# TakpadV6.net
KiCad netlist of a schematic drawn in EAGLE
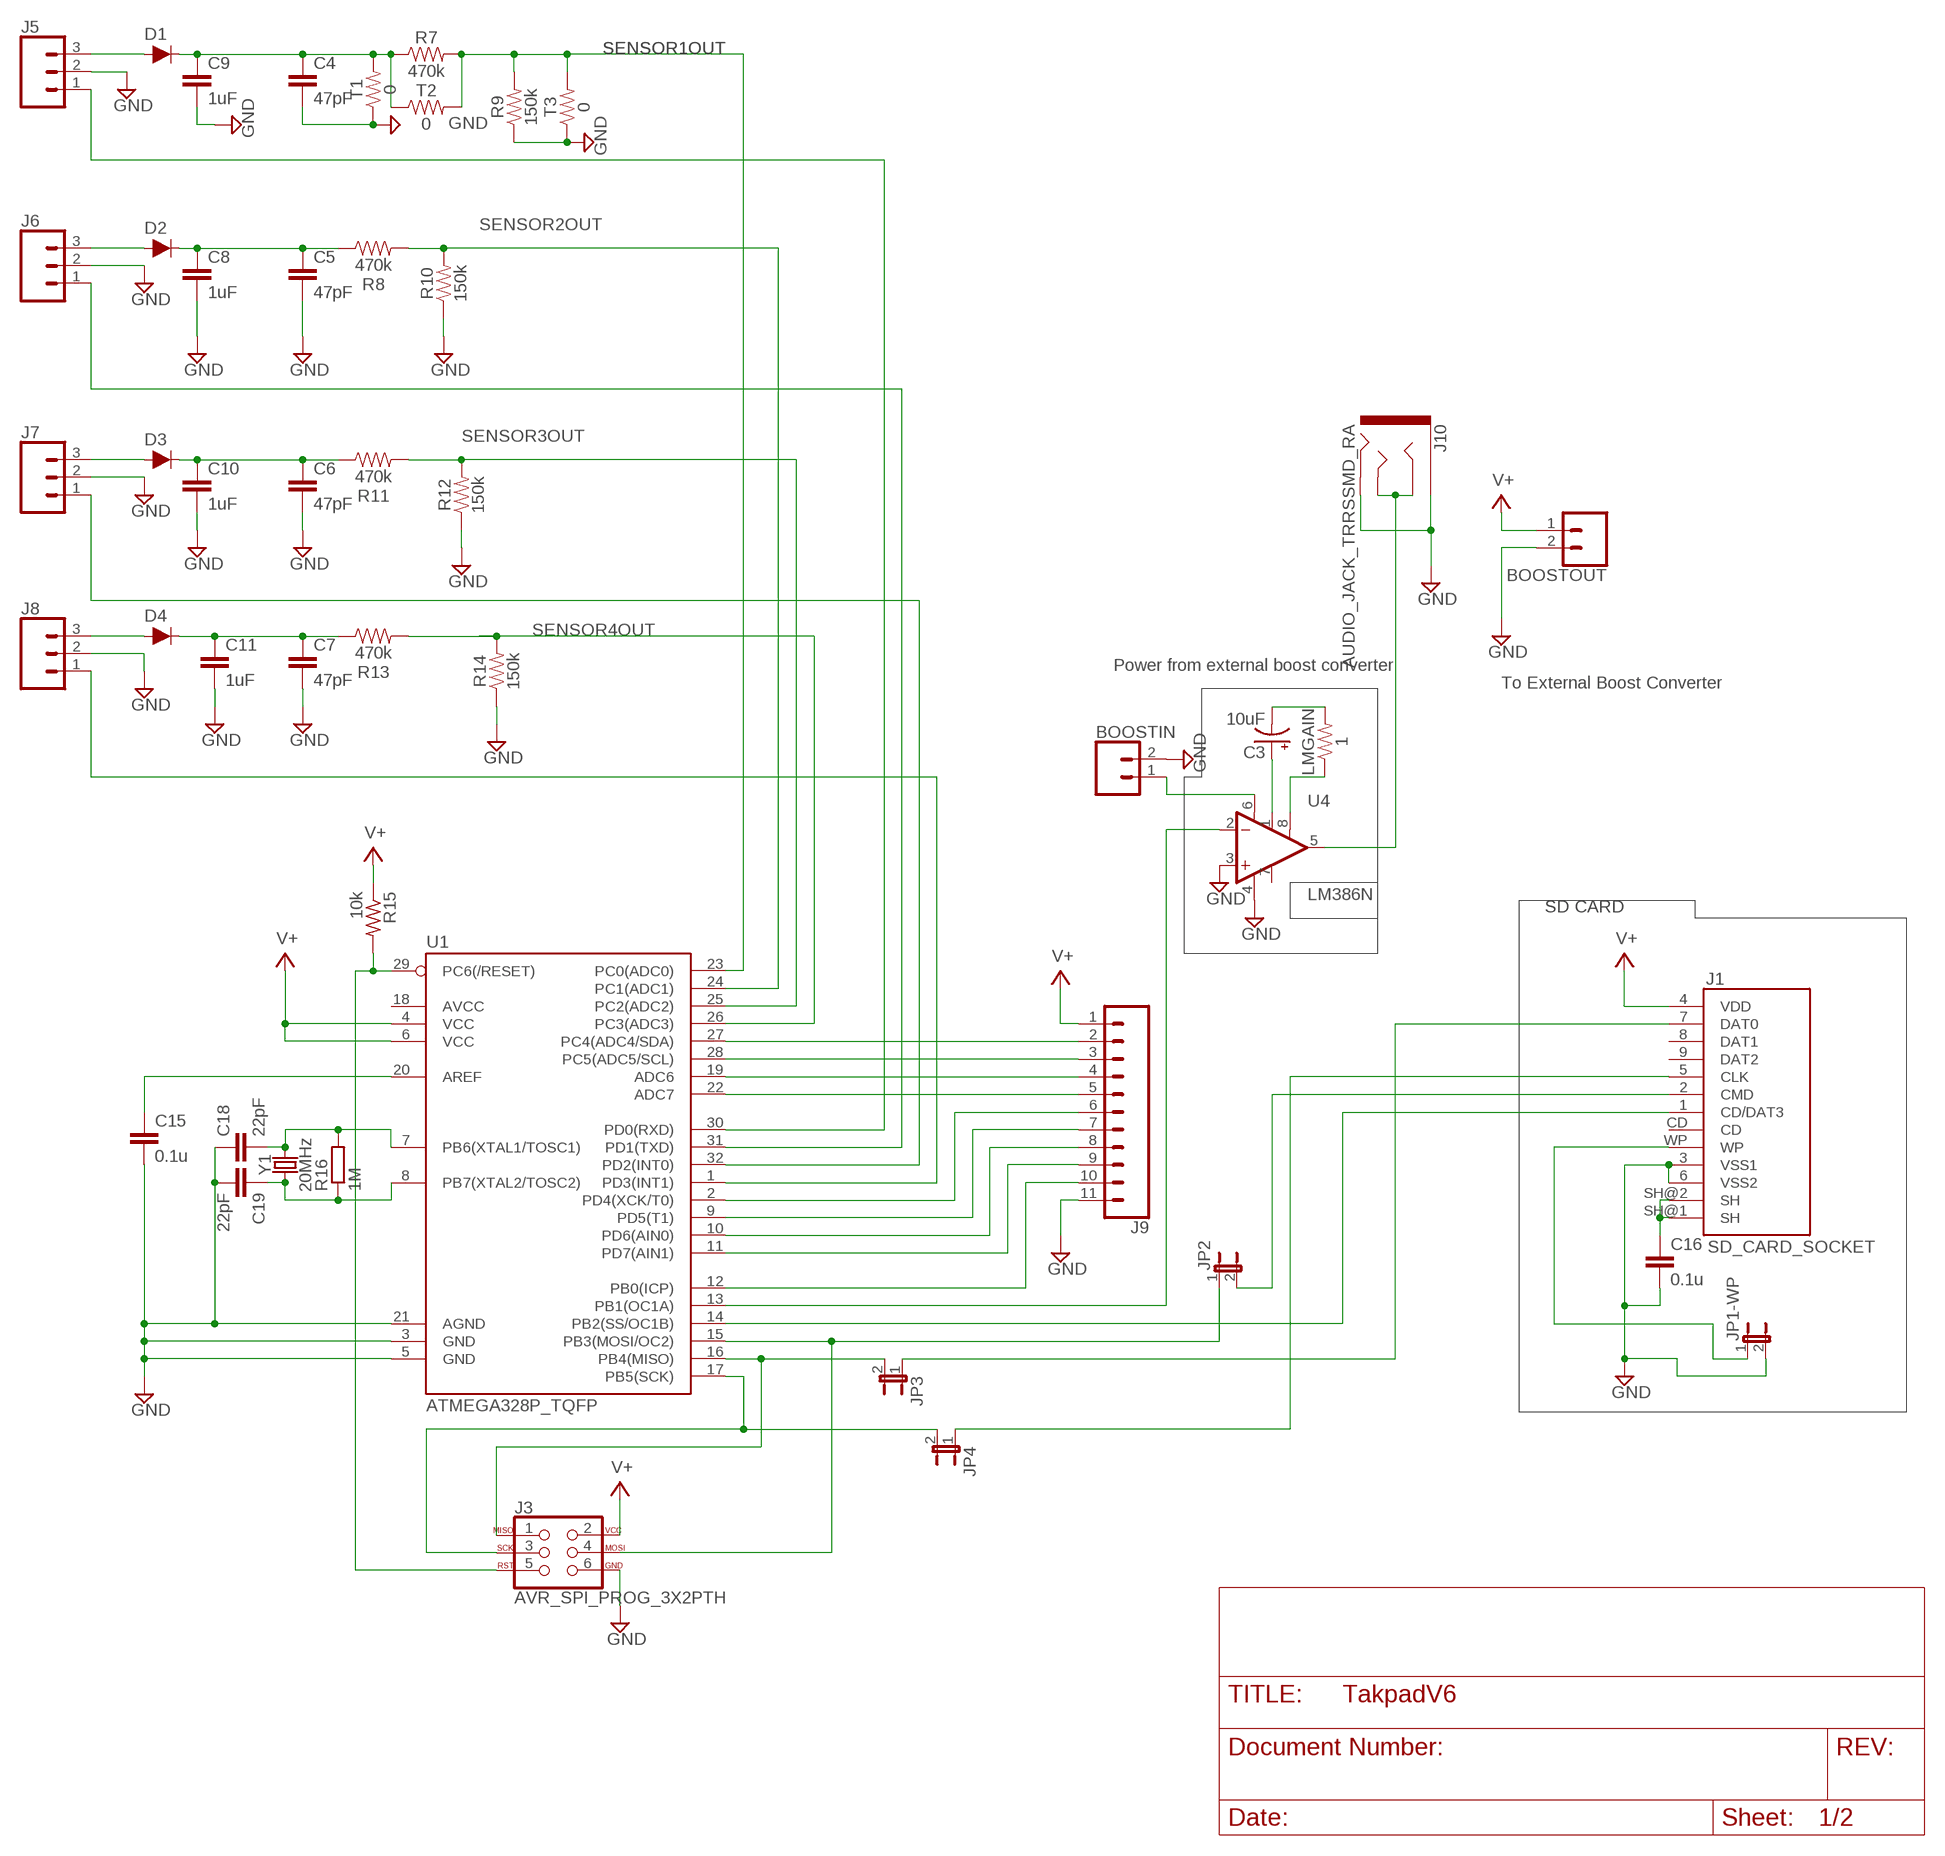
[diagram p0: schematic, sheet 1]
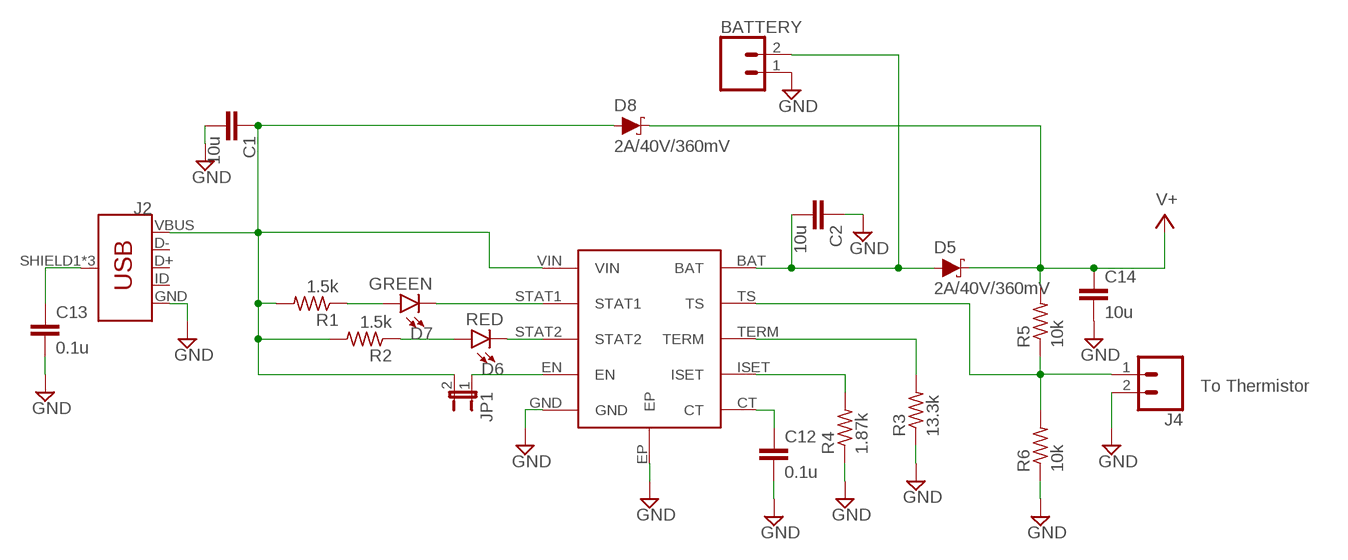
[diagram p1: schematic, sheet 2]

(export (version "E")
  (design (tool "Eeschema 10.0.6"))
  (components
    (comp (ref "BATTERY")
      (value "CONN_02")
      (footprint "eagle-import:1X02")
      (libsource (lib "eagle-import") (part "CONN_02"))
    )
    (comp (ref "C1")
      (value "10u")
      (footprint "eagle-import:C0402")
      (libsource (lib "eagle-import") (part "C-EUC0402"))
    )
    (comp (ref "C2")
      (value "10u")
      (footprint "eagle-import:C0402")
      (libsource (lib "eagle-import") (part "C-EUC0402"))
    )
    (comp (ref "C12")
      (value "0.1u")
      (footprint "eagle-import:C0402")
      (libsource (lib "eagle-import") (part "C-EUC0402"))
    )
    (comp (ref "C13")
      (value "0.1u")
      (footprint "eagle-import:C0402")
      (libsource (lib "eagle-import") (part "C-EUC0402"))
    )
    (comp (ref "C14")
      (value "10u")
      (footprint "eagle-import:C0402")
      (libsource (lib "eagle-import") (part "C-EUC0402"))
    )
    (comp (ref "D5")
      (value "2A/40V/360mV")
      (footprint "eagle-import:SMA-DIODE")
      (libsource (lib "eagle-import") (part "DIODE-SCHOTTKY-B340A"))
    )
    (comp (ref "D6")
      (value "RED")
      (footprint "eagle-import:LED-1206")
      (libsource (lib "eagle-import") (part "LED-RED1206"))
    )
    (comp (ref "D7")
      (value "GREEN")
      (footprint "eagle-import:LED-1206")
      (libsource (lib "eagle-import") (part "LED-GREEN1206"))
    )
    (comp (ref "D8")
      (value "2A/40V/360mV")
      (footprint "eagle-import:SMA-DIODE")
      (libsource (lib "eagle-import") (part "DIODE-SCHOTTKY-B340A"))
    )
    (comp (ref "J2")
      (value "USB_MICRO-BREDUCED_PASTE")
      (footprint "eagle-import:USB-B-MICRO-SMD_RED_PASTE")
      (libsource (lib "eagle-import") (part "USB_MICRO-BREDUCED_PASTE"))
    )
    (comp (ref "J4")
      (value "CONN_02")
      (footprint "eagle-import:1X02")
      (libsource (lib "eagle-import") (part "CONN_02"))
    )
    (comp (ref "JP1")
      (value "JUMPER-2PTH")
      (footprint "eagle-import:1X02")
      (libsource (lib "eagle-import") (part "JUMPER-2PTH"))
    )
    (comp (ref "R1")
      (value "1.5k")
      (footprint "eagle-import:M1206")
      (libsource (lib "eagle-import") (part "R-US_M1206"))
    )
    (comp (ref "R2")
      (value "1.5k")
      (footprint "eagle-import:M1206")
      (libsource (lib "eagle-import") (part "R-US_M1206"))
    )
    (comp (ref "R3")
      (value "13.3k")
      (footprint "eagle-import:M1206")
      (libsource (lib "eagle-import") (part "R-US_M1206"))
    )
    (comp (ref "R4")
      (value "1.87k")
      (footprint "eagle-import:M1206")
      (libsource (lib "eagle-import") (part "R-US_M1206"))
    )
    (comp (ref "R5")
      (value "10k")
      (footprint "eagle-import:M1206")
      (libsource (lib "eagle-import") (part "R-US_M1206"))
    )
    (comp (ref "R6")
      (value "10k")
      (footprint "eagle-import:M1206")
      (libsource (lib "eagle-import") (part "R-US_M1206"))
    )
    (comp (ref "U$1")
      (value "AAT3693")
      (footprint "eagle-import:IDH-AA-T1")
      (libsource (lib "eagle-import") (part "AAT3693"))
    )
    (comp (ref "BOOSTIN")
      (value "CONN_02")
      (footprint "eagle-import:1X02")
      (libsource (lib "eagle-import") (part "CONN_02"))
    )
    (comp (ref "BOOSTOUT")
      (value "CONN_02")
      (footprint "eagle-import:1X02")
      (libsource (lib "eagle-import") (part "CONN_02"))
    )
    (comp (ref "C3")
      (value "10uF")
      (footprint "eagle-import:CPOL-RADIAL-2.5MM-5MM-KIT")
      (libsource (lib "eagle-import") (part "10UF-POLAR-RADIAL-2.5MM-KIT-25V-20%"))
    )
    (comp (ref "C4")
      (value "47pF")
      (footprint "eagle-import:0603")
      (libsource (lib "eagle-import") (part "47PF-0603-50V-5%"))
    )
    (comp (ref "C5")
      (value "47pF")
      (footprint "eagle-import:0603")
      (libsource (lib "eagle-import") (part "47PF-0603-50V-5%"))
    )
    (comp (ref "C6")
      (value "47pF")
      (footprint "eagle-import:0603")
      (libsource (lib "eagle-import") (part "47PF-0603-50V-5%"))
    )
    (comp (ref "C7")
      (value "47pF")
      (footprint "eagle-import:0603")
      (libsource (lib "eagle-import") (part "47PF-0603-50V-5%"))
    )
    (comp (ref "C8")
      (value "1uF")
      (footprint "eagle-import:0603")
      (libsource (lib "eagle-import") (part "47PF-0603-50V-5%"))
    )
    (comp (ref "C9")
      (value "1uF")
      (footprint "eagle-import:0603")
      (libsource (lib "eagle-import") (part "47PF-0603-50V-5%"))
    )
    (comp (ref "C10")
      (value "1uF")
      (footprint "eagle-import:0603")
      (libsource (lib "eagle-import") (part "47PF-0603-50V-5%"))
    )
    (comp (ref "C11")
      (value "1uF")
      (footprint "eagle-import:0603")
      (libsource (lib "eagle-import") (part "47PF-0603-50V-5%"))
    )
    (comp (ref "C15")
      (value "0.1u")
      (footprint "eagle-import:C0402")
      (libsource (lib "eagle-import") (part "C-EUC0402"))
    )
    (comp (ref "C16")
      (value "0.1u")
      (footprint "eagle-import:C0402")
      (libsource (lib "eagle-import") (part "C-EUC0402"))
    )
    (comp (ref "C18")
      (value "22pF")
      (footprint "eagle-import:C0402")
      (libsource (lib "eagle-import") (part "resistor_348_C-EUC0402"))
    )
    (comp (ref "C19")
      (value "22pF")
      (footprint "eagle-import:C0402")
      (libsource (lib "eagle-import") (part "resistor_348_C-EUC0402"))
    )
    (comp (ref "D1")
      (value "200mA/100V/1V")
      (footprint "eagle-import:DIODE-1N4148")
      (libsource (lib "eagle-import") (part "DIODE-1N4148"))
    )
    (comp (ref "D2")
      (value "200mA/100V/1V")
      (footprint "eagle-import:DIODE-1N4148")
      (libsource (lib "eagle-import") (part "DIODE-1N4148"))
    )
    (comp (ref "D3")
      (value "200mA/100V/1V")
      (footprint "eagle-import:DIODE-1N4148")
      (libsource (lib "eagle-import") (part "DIODE-1N4148"))
    )
    (comp (ref "D4")
      (value "200mA/100V/1V")
      (footprint "eagle-import:DIODE-1N4148")
      (libsource (lib "eagle-import") (part "DIODE-1N4148"))
    )
    (comp (ref "J1")
      (value "SD_CARD_SOCKET")
      (footprint "eagle-import:SD")
      (libsource (lib "eagle-import") (part "SD_CARD_SOCKET"))
    )
    (comp (ref "J3")
      (value "AVR_SPI_PROG_3X2PTH")
      (footprint "eagle-import:2X3")
      (libsource (lib "eagle-import") (part "AVR_SPI_PROG_3X2PTH"))
    )
    (comp (ref "J5")
      (value "CONN_03")
      (footprint "eagle-import:1X03")
      (libsource (lib "eagle-import") (part "CONN_03"))
    )
    (comp (ref "J6")
      (value "CONN_03")
      (footprint "eagle-import:1X03")
      (libsource (lib "eagle-import") (part "CONN_03"))
    )
    (comp (ref "J7")
      (value "CONN_03")
      (footprint "eagle-import:1X03")
      (libsource (lib "eagle-import") (part "CONN_03"))
    )
    (comp (ref "J8")
      (value "CONN_03")
      (footprint "eagle-import:1X03")
      (libsource (lib "eagle-import") (part "CONN_03"))
    )
    (comp (ref "J9")
      (value "CONN_11")
      (footprint "eagle-import:1X11")
      (libsource (lib "eagle-import") (part "CONN_11"))
    )
    (comp (ref "J10")
      (value "AUDIO_JACK_TRRSSMD_RA")
      (footprint "eagle-import:AUDIO_JACK_3.5MM_TRRS_SMD_RA")
      (libsource (lib "eagle-import") (part "AUDIO_JACK_TRRSSMD_RA"))
    )
    (comp (ref "JP1-WP")
      (value "JUMPER-2PTH")
      (footprint "eagle-import:1X02")
      (libsource (lib "eagle-import") (part "JUMPER-2PTH"))
    )
    (comp (ref "JP2")
      (value "JUMPER-2PTH")
      (footprint "eagle-import:1X02")
      (libsource (lib "eagle-import") (part "JUMPER-2PTH"))
    )
    (comp (ref "JP3")
      (value "JUMPER-2PTH")
      (footprint "eagle-import:1X02")
      (libsource (lib "eagle-import") (part "JUMPER-2PTH"))
    )
    (comp (ref "JP4")
      (value "JUMPER-2PTH")
      (footprint "eagle-import:1X02")
      (libsource (lib "eagle-import") (part "JUMPER-2PTH"))
    )
    (comp (ref "LMGAIN")
      (value "1")
      (footprint "eagle-import:0603")
      (libsource (lib "eagle-import") (part "1OHM-0603-1/10W-1%"))
    )
    (comp (ref "R7")
      (value "470k")
      (footprint "eagle-import:AXIAL-0.3")
      (libsource (lib "eagle-import") (part "1KOHM-HORIZ-1/4W-1%"))
    )
    (comp (ref "R8")
      (value "470k")
      (footprint "eagle-import:AXIAL-0.3")
      (libsource (lib "eagle-import") (part "1KOHM-HORIZ-1/4W-1%"))
    )
    (comp (ref "R9")
      (value "150k")
      (footprint "eagle-import:AXIAL-0.3")
      (libsource (lib "eagle-import") (part "1KOHM-HORIZ-1/4W-1%"))
    )
    (comp (ref "R10")
      (value "150k")
      (footprint "eagle-import:AXIAL-0.3")
      (libsource (lib "eagle-import") (part "1KOHM-HORIZ-1/4W-1%"))
    )
    (comp (ref "R11")
      (value "470k")
      (footprint "eagle-import:AXIAL-0.3")
      (libsource (lib "eagle-import") (part "1KOHM-HORIZ-1/4W-1%"))
    )
    (comp (ref "R12")
      (value "150k")
      (footprint "eagle-import:AXIAL-0.3")
      (libsource (lib "eagle-import") (part "1KOHM-HORIZ-1/4W-1%"))
    )
    (comp (ref "R13")
      (value "470k")
      (footprint "eagle-import:AXIAL-0.3")
      (libsource (lib "eagle-import") (part "1KOHM-HORIZ-1/4W-1%"))
    )
    (comp (ref "R14")
      (value "150k")
      (footprint "eagle-import:AXIAL-0.3")
      (libsource (lib "eagle-import") (part "1KOHM-HORIZ-1/4W-1%"))
    )
    (comp (ref "R15")
      (value "10k")
      (footprint "eagle-import:M1206")
      (libsource (lib "eagle-import") (part "R-US_M1206"))
    )
    (comp (ref "R16")
      (value "1M")
      (footprint "eagle-import:R0402")
      (libsource (lib "eagle-import") (part "R-EU_R0402"))
    )
    (comp (ref "T1")
      (value "0")
      (footprint "eagle-import:AXIAL-0.3")
      (libsource (lib "eagle-import") (part "1KOHM-HORIZ-1/4W-1%"))
    )
    (comp (ref "T2")
      (value "0")
      (footprint "eagle-import:AXIAL-0.3")
      (libsource (lib "eagle-import") (part "1KOHM-HORIZ-1/4W-1%"))
    )
    (comp (ref "T3")
      (value "0")
      (footprint "eagle-import:AXIAL-0.3")
      (libsource (lib "eagle-import") (part "1KOHM-HORIZ-1/4W-1%"))
    )
    (comp (ref "U1")
      (value "ATMEGA328P_TQFP")
      (footprint "eagle-import:TQFP32-08")
      (libsource (lib "eagle-import") (part "ATMEGA328P_TQFP"))
    )
    (comp (ref "U4")
      (value "LM386N")
      (footprint "eagle-import:DIP08")
      (libsource (lib "eagle-import") (part "LM386"))
    )
    (comp (ref "Y1")
      (value "20MHz")
      (footprint "eagle-import:HC49US")
      (libsource (lib "eagle-import") (part "CRYSTAL-16MHZPTH-HC49US"))
    )
  )
  (nets
    (net (code "1") (name "GND") (class "Default")
      (node (ref "BATTERY") (pin "1") (pinfunction "1_1") (pintype "passive"))
      (node (ref "BOOSTIN") (pin "2") (pinfunction "2_2") (pintype "passive"))
      (node (ref "BOOSTOUT") (pin "2") (pinfunction "2_2") (pintype "passive"))
      (node (ref "C1") (pin "2") (pinfunction "2_2") (pintype "passive"))
      (node (ref "C10") (pin "2") (pinfunction "2_2") (pintype "passive"))
      (node (ref "C11") (pin "2") (pinfunction "2_2") (pintype "passive"))
      (node (ref "C12") (pin "2") (pinfunction "2_2") (pintype "passive"))
      (node (ref "C13") (pin "2") (pinfunction "2_2") (pintype "passive"))
      (node (ref "C14") (pin "2") (pinfunction "2_2") (pintype "passive"))
      (node (ref "C15") (pin "2") (pinfunction "2_2") (pintype "passive"))
      (node (ref "C16") (pin "2") (pinfunction "2_2") (pintype "passive"))
      (node (ref "C18") (pin "1") (pinfunction "1_1") (pintype "passive"))
      (node (ref "C19") (pin "2") (pinfunction "2_2") (pintype "passive"))
      (node (ref "C2") (pin "1") (pinfunction "1_1") (pintype "passive"))
      (node (ref "C4") (pin "2") (pinfunction "2_2") (pintype "passive"))
      (node (ref "C5") (pin "2") (pinfunction "2_2") (pintype "passive"))
      (node (ref "C6") (pin "2") (pinfunction "2_2") (pintype "passive"))
      (node (ref "C7") (pin "2") (pinfunction "2_2") (pintype "passive"))
      (node (ref "C8") (pin "2") (pinfunction "2_2") (pintype "passive"))
      (node (ref "C9") (pin "2") (pinfunction "2_2") (pintype "passive"))
      (node (ref "J1") (pin "3") (pinfunction "VSS1_3") (pintype "power_in"))
      (node (ref "J1") (pin "6") (pinfunction "VSS2_6") (pintype "power_in"))
      (node (ref "J10") (pin "EARTH") (pinfunction "EARTH_EARTH") (pintype "bidirectional"))
      (node (ref "J10") (pin "RING2") (pinfunction "RING2_RING2") (pintype "bidirectional"))
      (node (ref "J2") (pin "GND") (pinfunction "GND_GND") (pintype "power_in"))
      (node (ref "J3") (pin "6") (pinfunction "6_6") (pintype "passive"))
      (node (ref "J4") (pin "2") (pinfunction "2_2") (pintype "passive"))
      (node (ref "J5") (pin "2") (pinfunction "2_2") (pintype "passive"))
      (node (ref "J6") (pin "2") (pinfunction "2_2") (pintype "passive"))
      (node (ref "J7") (pin "2") (pinfunction "2_2") (pintype "passive"))
      (node (ref "J8") (pin "2") (pinfunction "2_2") (pintype "passive"))
      (node (ref "J9") (pin "11") (pinfunction "11_11") (pintype "passive"))
      (node (ref "JP1-WP") (pin "2") (pinfunction "2_2") (pintype "passive"))
      (node (ref "R10") (pin "P$1") (pinfunction "1_P$1") (pintype "passive"))
      (node (ref "R12") (pin "P$1") (pinfunction "1_P$1") (pintype "passive"))
      (node (ref "R14") (pin "P$1") (pinfunction "1_P$1") (pintype "passive"))
      (node (ref "R3") (pin "1") (pinfunction "1_1") (pintype "passive"))
      (node (ref "R4") (pin "1") (pinfunction "1_1") (pintype "passive"))
      (node (ref "R6") (pin "1") (pinfunction "1_1") (pintype "passive"))
      (node (ref "R9") (pin "P$1") (pinfunction "1_P$1") (pintype "passive"))
      (node (ref "T1") (pin "P$1") (pinfunction "1_P$1") (pintype "passive"))
      (node (ref "T3") (pin "P$1") (pinfunction "1_P$1") (pintype "passive"))
      (node (ref "U$1") (pin "EP") (pinfunction "EP_EP") (pintype "bidirectional"))
      (node (ref "U$1") (pin "GND") (pinfunction "GND_GND") (pintype "bidirectional"))
      (node (ref "U1") (pin "21") (pinfunction "AGND_21") (pintype "bidirectional"))
      (node (ref "U1") (pin "3") (pinfunction "GND_3") (pintype "bidirectional"))
      (node (ref "U1") (pin "5") (pinfunction "GND_5") (pintype "bidirectional"))
      (node (ref "U4") (pin "3") (pinfunction "+IN_3") (pintype "input"))
      (node (ref "U4") (pin "4") (pinfunction "V-_4") (pintype "power_in"))
    )
    (net (code "2") (name "Net-(BATTERY-Pad2)") (class "Default")
      (node (ref "BATTERY") (pin "2") (pinfunction "2_2") (pintype "passive"))
      (node (ref "C2") (pin "2") (pinfunction "2_2") (pintype "passive"))
      (node (ref "D5") (pin "A") (pinfunction "A_A") (pintype "passive"))
      (node (ref "U$1") (pin "BAT") (pinfunction "BAT_BAT") (pintype "bidirectional"))
    )
    (net (code "3") (name "Net-(C1-Pad1)") (class "Default")
      (node (ref "C1") (pin "1") (pinfunction "1_1") (pintype "passive"))
      (node (ref "D8") (pin "A") (pinfunction "A_A") (pintype "passive"))
      (node (ref "J2") (pin "VBUS") (pinfunction "VBUS_VBUS") (pintype "power_in"))
      (node (ref "JP1") (pin "2") (pinfunction "2_2") (pintype "passive"))
      (node (ref "R1") (pin "2") (pinfunction "2_2") (pintype "passive"))
      (node (ref "R2") (pin "2") (pinfunction "2_2") (pintype "passive"))
      (node (ref "U$1") (pin "VIN") (pinfunction "VIN_VIN") (pintype "bidirectional"))
    )
    (net (code "4") (name "Net-(C3-+)") (class "Default")
      (node (ref "C3") (pin "1") (pinfunction "+_1") (pintype "passive"))
      (node (ref "U4") (pin "1") (pinfunction "GAIN_1") (pintype "bidirectional"))
    )
    (net (code "5") (name "Net-(C3--)") (class "Default")
      (node (ref "C3") (pin "2") (pinfunction "-_2") (pintype "passive"))
      (node (ref "LMGAIN") (pin "2") (pinfunction "2_2") (pintype "passive"))
    )
    (net (code "6") (name "Net-(C12-Pad1)") (class "Default")
      (node (ref "C12") (pin "1") (pinfunction "1_1") (pintype "passive"))
      (node (ref "U$1") (pin "CT") (pinfunction "CT_CT") (pintype "bidirectional"))
    )
    (net (code "7") (name "Net-(C13-Pad1)") (class "Default")
      (node (ref "C13") (pin "1") (pinfunction "1_1") (pintype "passive"))
      (node (ref "J2") (pin "SHIELD1") (pinfunction "SHIELD_SHIELD1") (pintype "bidirectional"))
      (node (ref "J2") (pin "SHIELD2") (pinfunction "SHIELD_SHIELD2") (pintype "bidirectional"))
      (node (ref "J2") (pin "SHIELD3") (pinfunction "SHIELD_SHIELD3") (pintype "bidirectional"))
    )
    (net (code "8") (name "Net-(C16-Pad1)") (class "Default")
      (node (ref "C16") (pin "1") (pinfunction "1_1") (pintype "passive"))
      (node (ref "J1") (pin "SH@1") (pinfunction "SH_SH@1") (pintype "bidirectional"))
      (node (ref "J1") (pin "SH@2") (pinfunction "SH_SH@2") (pintype "bidirectional"))
    )
    (net (code "9") (name "Net-(D1-PadA)") (class "Default")
      (node (ref "D1") (pin "A") (pinfunction "A_A") (pintype "passive"))
      (node (ref "J5") (pin "3") (pinfunction "3_3") (pintype "passive"))
    )
    (net (code "10") (name "Net-(D2-PadA)") (class "Default")
      (node (ref "D2") (pin "A") (pinfunction "A_A") (pintype "passive"))
      (node (ref "J6") (pin "3") (pinfunction "3_3") (pintype "passive"))
    )
    (net (code "11") (name "Net-(D3-PadA)") (class "Default")
      (node (ref "D3") (pin "A") (pinfunction "A_A") (pintype "passive"))
      (node (ref "J7") (pin "3") (pinfunction "3_3") (pintype "passive"))
    )
    (net (code "12") (name "Net-(D4-PadA)") (class "Default")
      (node (ref "D4") (pin "A") (pinfunction "A_A") (pintype "passive"))
      (node (ref "J8") (pin "3") (pinfunction "3_3") (pintype "passive"))
    )
    (net (code "13") (name "Net-(D6-PadA)") (class "Default")
      (node (ref "D6") (pin "A") (pinfunction "A_A") (pintype "passive"))
      (node (ref "R2") (pin "1") (pinfunction "1_1") (pintype "passive"))
    )
    (net (code "14") (name "Net-(D6-PadC)") (class "Default")
      (node (ref "D6") (pin "C") (pinfunction "C_C") (pintype "passive"))
      (node (ref "U$1") (pin "STAT2") (pinfunction "STAT2_STAT2") (pintype "bidirectional"))
    )
    (net (code "15") (name "Net-(D7-PadA)") (class "Default")
      (node (ref "D7") (pin "A") (pinfunction "A_A") (pintype "passive"))
      (node (ref "R1") (pin "1") (pinfunction "1_1") (pintype "passive"))
    )
    (net (code "16") (name "Net-(D7-PadC)") (class "Default")
      (node (ref "D7") (pin "C") (pinfunction "C_C") (pintype "passive"))
      (node (ref "U$1") (pin "STAT1") (pinfunction "STAT1_STAT1") (pintype "bidirectional"))
    )
    (net (code "17") (name "Net-(J1-CD{slash}DAT3)") (class "Default")
      (node (ref "J1") (pin "1") (pinfunction "CD/DAT3_1") (pintype "bidirectional"))
      (node (ref "U1") (pin "14") (pinfunction "PB2(SS/OC1B)_14") (pintype "bidirectional"))
    )
    (net (code "18") (name "Net-(J1-CLK)") (class "Default")
      (node (ref "J1") (pin "5") (pinfunction "CLK_5") (pintype "bidirectional"))
      (node (ref "JP4") (pin "1") (pinfunction "1_1") (pintype "passive"))
    )
    (net (code "19") (name "Net-(J1-CMD)") (class "Default")
      (node (ref "J1") (pin "2") (pinfunction "CMD_2") (pintype "bidirectional"))
      (node (ref "JP2") (pin "2") (pinfunction "2_2") (pintype "passive"))
    )
    (net (code "20") (name "Net-(J1-DAT0)") (class "Default")
      (node (ref "J1") (pin "7") (pinfunction "DAT0_7") (pintype "bidirectional"))
      (node (ref "JP3") (pin "1") (pinfunction "1_1") (pintype "passive"))
    )
    (net (code "21") (name "Net-(J1-PadWP)") (class "Default")
      (node (ref "J1") (pin "WP") (pinfunction "WP_WP") (pintype "bidirectional"))
      (node (ref "JP1-WP") (pin "1") (pinfunction "1_1") (pintype "passive"))
    )
    (net (code "22") (name "Net-(J4-Pad1)") (class "Default")
      (node (ref "J4") (pin "1") (pinfunction "1_1") (pintype "passive"))
      (node (ref "R5") (pin "1") (pinfunction "1_1") (pintype "passive"))
      (node (ref "R6") (pin "2") (pinfunction "2_2") (pintype "passive"))
      (node (ref "U$1") (pin "TS") (pinfunction "TS_TS") (pintype "bidirectional"))
    )
    (net (code "23") (name "Net-(JP1-Pad1)") (class "Default")
      (node (ref "JP1") (pin "1") (pinfunction "1_1") (pintype "passive"))
      (node (ref "U$1") (pin "EN") (pinfunction "EN_EN") (pintype "bidirectional"))
    )
    (net (code "24") (name "Net-(LMGAIN-Pad1)") (class "Default")
      (node (ref "LMGAIN") (pin "1") (pinfunction "1_1") (pintype "passive"))
      (node (ref "U4") (pin "8") (pinfunction "GAIN_8") (pintype "bidirectional"))
    )
    (net (code "25") (name "Net-(R3-Pad2)") (class "Default")
      (node (ref "R3") (pin "2") (pinfunction "2_2") (pintype "passive"))
      (node (ref "U$1") (pin "TERM") (pinfunction "TERM_TERM") (pintype "bidirectional"))
    )
    (net (code "26") (name "Net-(R4-Pad2)") (class "Default")
      (node (ref "R4") (pin "2") (pinfunction "2_2") (pintype "passive"))
      (node (ref "U$1") (pin "ISET") (pinfunction "ISET_ISET") (pintype "bidirectional"))
    )
    (net (code "27") (name "Net-(R7-1)") (class "Default")
      (node (ref "C4") (pin "1") (pinfunction "1_1") (pintype "passive"))
      (node (ref "C9") (pin "1") (pinfunction "1_1") (pintype "passive"))
      (node (ref "D1") (pin "C") (pinfunction "C_C") (pintype "passive"))
      (node (ref "R7") (pin "P$1") (pinfunction "1_P$1") (pintype "passive"))
      (node (ref "T1") (pin "P$2") (pinfunction "2_P$2") (pintype "passive"))
      (node (ref "T2") (pin "P$1") (pinfunction "1_P$1") (pintype "passive"))
    )
    (net (code "28") (name "Net-(R8-1)") (class "Default")
      (node (ref "C5") (pin "1") (pinfunction "1_1") (pintype "passive"))
      (node (ref "C8") (pin "1") (pinfunction "1_1") (pintype "passive"))
      (node (ref "D2") (pin "C") (pinfunction "C_C") (pintype "passive"))
      (node (ref "R8") (pin "P$1") (pinfunction "1_P$1") (pintype "passive"))
    )
    (net (code "29") (name "Net-(R11-1)") (class "Default")
      (node (ref "C10") (pin "1") (pinfunction "1_1") (pintype "passive"))
      (node (ref "C6") (pin "1") (pinfunction "1_1") (pintype "passive"))
      (node (ref "D3") (pin "C") (pinfunction "C_C") (pintype "passive"))
      (node (ref "R11") (pin "P$1") (pinfunction "1_P$1") (pintype "passive"))
    )
    (net (code "30") (name "Net-(R13-1)") (class "Default")
      (node (ref "C11") (pin "1") (pinfunction "1_1") (pintype "passive"))
      (node (ref "C7") (pin "1") (pinfunction "1_1") (pintype "passive"))
      (node (ref "D4") (pin "C") (pinfunction "C_C") (pintype "passive"))
      (node (ref "R13") (pin "P$1") (pinfunction "1_P$1") (pintype "passive"))
    )
    (net (code "31") (name "Net-(U1-ADC6)") (class "Default")
      (node (ref "J9") (pin "4") (pinfunction "4_4") (pintype "passive"))
      (node (ref "U1") (pin "19") (pinfunction "ADC6_19") (pintype "bidirectional"))
    )
    (net (code "32") (name "Net-(U1-ADC7)") (class "Default")
      (node (ref "J9") (pin "5") (pinfunction "5_5") (pintype "passive"))
      (node (ref "U1") (pin "22") (pinfunction "ADC7_22") (pintype "bidirectional"))
    )
    (net (code "33") (name "Net-(U1-AREF)") (class "Default")
      (node (ref "C15") (pin "1") (pinfunction "1_1") (pintype "passive"))
      (node (ref "U1") (pin "20") (pinfunction "AREF_20") (pintype "bidirectional"))
    )
    (net (code "34") (name "Net-(U1-PB0(ICP))") (class "Default")
      (node (ref "J9") (pin "10") (pinfunction "10_10") (pintype "passive"))
      (node (ref "U1") (pin "12") (pinfunction "PB0(ICP)_12") (pintype "bidirectional"))
    )
    (net (code "35") (name "Net-(U1-PB1(OC1A))") (class "Default")
      (node (ref "U1") (pin "13") (pinfunction "PB1(OC1A)_13") (pintype "bidirectional"))
      (node (ref "U4") (pin "2") (pinfunction "-IN_2") (pintype "input"))
    )
    (net (code "36") (name "Net-(U1-PB3(MOSI{slash}OC2))") (class "Default")
      (node (ref "J3") (pin "4") (pinfunction "4_4") (pintype "passive"))
      (node (ref "JP2") (pin "1") (pinfunction "1_1") (pintype "passive"))
      (node (ref "U1") (pin "15") (pinfunction "PB3(MOSI/OC2)_15") (pintype "bidirectional"))
    )
    (net (code "37") (name "Net-(U1-PB4(MISO))") (class "Default")
      (node (ref "J3") (pin "1") (pinfunction "1_1") (pintype "passive"))
      (node (ref "JP3") (pin "2") (pinfunction "2_2") (pintype "passive"))
      (node (ref "U1") (pin "16") (pinfunction "PB4(MISO)_16") (pintype "bidirectional"))
    )
    (net (code "38") (name "Net-(U1-PB5(SCK))") (class "Default")
      (node (ref "J3") (pin "3") (pinfunction "3_3") (pintype "passive"))
      (node (ref "JP4") (pin "2") (pinfunction "2_2") (pintype "passive"))
      (node (ref "U1") (pin "17") (pinfunction "PB5(SCK)_17") (pintype "bidirectional"))
    )
    (net (code "39") (name "Net-(U1-PB6(XTAL1{slash}TOSC1))") (class "Default")
      (node (ref "C18") (pin "2") (pinfunction "2_2") (pintype "passive"))
      (node (ref "R16") (pin "2") (pinfunction "2_2") (pintype "passive"))
      (node (ref "U1") (pin "7") (pinfunction "PB6(XTAL1/TOSC1)_7") (pintype "bidirectional"))
      (node (ref "Y1") (pin "2") (pinfunction "2_2") (pintype "passive"))
    )
    (net (code "40") (name "Net-(U1-PB7(XTAL2{slash}TOSC2))") (class "Default")
      (node (ref "C19") (pin "1") (pinfunction "1_1") (pintype "passive"))
      (node (ref "R16") (pin "1") (pinfunction "1_1") (pintype "passive"))
      (node (ref "U1") (pin "8") (pinfunction "PB7(XTAL2/TOSC2)_8") (pintype "bidirectional"))
      (node (ref "Y1") (pin "1") (pinfunction "1_1") (pintype "passive"))
    )
    (net (code "41") (name "Net-(U1-PC4(ADC4{slash}SDA))") (class "Default")
      (node (ref "J9") (pin "2") (pinfunction "2_2") (pintype "passive"))
      (node (ref "U1") (pin "27") (pinfunction "PC4(ADC4/SDA)_27") (pintype "bidirectional"))
    )
    (net (code "42") (name "Net-(U1-PC5(ADC5{slash}SCL))") (class "Default")
      (node (ref "J9") (pin "3") (pinfunction "3_3") (pintype "passive"))
      (node (ref "U1") (pin "28") (pinfunction "PC5(ADC5/SCL)_28") (pintype "bidirectional"))
    )
    (net (code "43") (name "Net-(U1-PC6({slash}RESET))") (class "Default")
      (node (ref "J3") (pin "5") (pinfunction "5_5") (pintype "passive"))
      (node (ref "R15") (pin "2") (pinfunction "2_2") (pintype "passive"))
      (node (ref "U1") (pin "29") (pinfunction "PC6(/RESET)_29") (pintype "bidirectional"))
    )
    (net (code "44") (name "Net-(U1-PD0(RXD))") (class "Default")
      (node (ref "J5") (pin "1") (pinfunction "1_1") (pintype "passive"))
      (node (ref "U1") (pin "30") (pinfunction "PD0(RXD)_30") (pintype "bidirectional"))
    )
    (net (code "45") (name "Net-(U1-PD1(TXD))") (class "Default")
      (node (ref "J6") (pin "1") (pinfunction "1_1") (pintype "passive"))
      (node (ref "U1") (pin "31") (pinfunction "PD1(TXD)_31") (pintype "bidirectional"))
    )
    (net (code "46") (name "Net-(U1-PD2(INT0))") (class "Default")
      (node (ref "J7") (pin "1") (pinfunction "1_1") (pintype "passive"))
      (node (ref "U1") (pin "32") (pinfunction "PD2(INT0)_32") (pintype "bidirectional"))
    )
    (net (code "47") (name "Net-(U1-PD3(INT1))") (class "Default")
      (node (ref "J8") (pin "1") (pinfunction "1_1") (pintype "passive"))
      (node (ref "U1") (pin "1") (pinfunction "PD3(INT1)_1") (pintype "bidirectional"))
    )
    (net (code "48") (name "Net-(U1-PD4(XCK{slash}T0))") (class "Default")
      (node (ref "J9") (pin "6") (pinfunction "6_6") (pintype "passive"))
      (node (ref "U1") (pin "2") (pinfunction "PD4(XCK/T0)_2") (pintype "bidirectional"))
    )
    (net (code "49") (name "Net-(U1-PD5(T1))") (class "Default")
      (node (ref "J9") (pin "7") (pinfunction "7_7") (pintype "passive"))
      (node (ref "U1") (pin "9") (pinfunction "PD5(T1)_9") (pintype "bidirectional"))
    )
    (net (code "50") (name "Net-(U1-PD6(AIN0))") (class "Default")
      (node (ref "J9") (pin "8") (pinfunction "8_8") (pintype "passive"))
      (node (ref "U1") (pin "10") (pinfunction "PD6(AIN0)_10") (pintype "bidirectional"))
    )
    (net (code "51") (name "Net-(U1-PD7(AIN1))") (class "Default")
      (node (ref "J9") (pin "9") (pinfunction "9_9") (pintype "passive"))
      (node (ref "U1") (pin "11") (pinfunction "PD7(AIN1)_11") (pintype "bidirectional"))
    )
    (net (code "52") (name "Net-(U4-OUT)") (class "Default")
      (node (ref "J10") (pin "RING1") (pinfunction "RING1_RING1") (pintype "bidirectional"))
      (node (ref "J10") (pin "TIP") (pinfunction "TIP_TIP") (pintype "bidirectional"))
      (node (ref "U4") (pin "5") (pinfunction "OUT_5") (pintype "output"))
    )
    (net (code "53") (name "Net-(U4-V+)") (class "Default")
      (node (ref "BOOSTIN") (pin "1") (pinfunction "1_1") (pintype "passive"))
      (node (ref "U4") (pin "6") (pinfunction "V+_6") (pintype "power_in"))
    )
    (net (code "54") (name "SENSOR1OUT") (class "Default")
      (node (ref "R7") (pin "P$2") (pinfunction "2_P$2") (pintype "passive"))
      (node (ref "R9") (pin "P$2") (pinfunction "2_P$2") (pintype "passive"))
      (node (ref "T2") (pin "P$2") (pinfunction "2_P$2") (pintype "passive"))
      (node (ref "T3") (pin "P$2") (pinfunction "2_P$2") (pintype "passive"))
      (node (ref "U1") (pin "23") (pinfunction "PC0(ADC0)_23") (pintype "bidirectional"))
    )
    (net (code "55") (name "SENSOR2OUT") (class "Default")
      (node (ref "R10") (pin "P$2") (pinfunction "2_P$2") (pintype "passive"))
      (node (ref "R8") (pin "P$2") (pinfunction "2_P$2") (pintype "passive"))
      (node (ref "U1") (pin "24") (pinfunction "PC1(ADC1)_24") (pintype "bidirectional"))
    )
    (net (code "56") (name "SENSOR3OUT") (class "Default")
      (node (ref "R11") (pin "P$2") (pinfunction "2_P$2") (pintype "passive"))
      (node (ref "R12") (pin "P$2") (pinfunction "2_P$2") (pintype "passive"))
      (node (ref "U1") (pin "25") (pinfunction "PC2(ADC2)_25") (pintype "bidirectional"))
    )
    (net (code "57") (name "SENSOR4OUT") (class "Default")
      (node (ref "R13") (pin "P$2") (pinfunction "2_P$2") (pintype "passive"))
      (node (ref "R14") (pin "P$2") (pinfunction "2_P$2") (pintype "passive"))
      (node (ref "U1") (pin "26") (pinfunction "PC3(ADC3)_26") (pintype "bidirectional"))
    )
    (net (code "58") (name "V+") (class "Default")
      (node (ref "BOOSTOUT") (pin "1") (pinfunction "1_1") (pintype "passive"))
      (node (ref "C14") (pin "1") (pinfunction "1_1") (pintype "passive"))
      (node (ref "D5") (pin "C") (pinfunction "C_C") (pintype "passive"))
      (node (ref "D8") (pin "C") (pinfunction "C_C") (pintype "passive"))
      (node (ref "J1") (pin "4") (pinfunction "VDD_4") (pintype "power_in"))
      (node (ref "J3") (pin "2") (pinfunction "2_2") (pintype "passive"))
      (node (ref "J9") (pin "1") (pinfunction "1_1") (pintype "passive"))
      (node (ref "R15") (pin "1") (pinfunction "1_1") (pintype "passive"))
      (node (ref "R5") (pin "2") (pinfunction "2_2") (pintype "passive"))
      (node (ref "U1") (pin "4") (pinfunction "VCC_4") (pintype "bidirectional"))
      (node (ref "U1") (pin "6") (pinfunction "VCC_6") (pintype "bidirectional"))
    )
    (net (code "59") (name "unconnected-(J1-DAT1-Pad8)") (class "Default")
      (node (ref "J1") (pin "8") (pinfunction "DAT1_8") (pintype "bidirectional"))
    )
    (net (code "60") (name "unconnected-(J1-DAT2-Pad9)") (class "Default")
      (node (ref "J1") (pin "9") (pinfunction "DAT2_9") (pintype "bidirectional"))
    )
    (net (code "61") (name "unconnected-(J1-PadCD)") (class "Default")
      (node (ref "J1") (pin "CD") (pinfunction "CD_CD") (pintype "bidirectional"))
    )
    (net (code "62") (name "unconnected-(J2-PadD+)") (class "Default")
      (node (ref "J2") (pin "D+") (pinfunction "D+_D+") (pintype "bidirectional"))
    )
    (net (code "63") (name "unconnected-(J2-PadD-)") (class "Default")
      (node (ref "J2") (pin "D-") (pinfunction "D-_D-") (pintype "bidirectional"))
    )
    (net (code "64") (name "unconnected-(J2-PadID)") (class "Default")
      (node (ref "J2") (pin "ID") (pinfunction "ID_ID") (pintype "bidirectional"))
    )
    (net (code "65") (name "unconnected-(U1-AVCC-Pad18)") (class "Default")
      (node (ref "U1") (pin "18") (pinfunction "AVCC_18") (pintype "bidirectional"))
    )
    (net (code "66") (name "unconnected-(U4-BP-Pad7)") (class "Default")
      (node (ref "U4") (pin "7") (pinfunction "BP_7") (pintype "bidirectional"))
    )
  )
)
